# power.net
KiCad netlist of a schematic drawn in Altium Designer
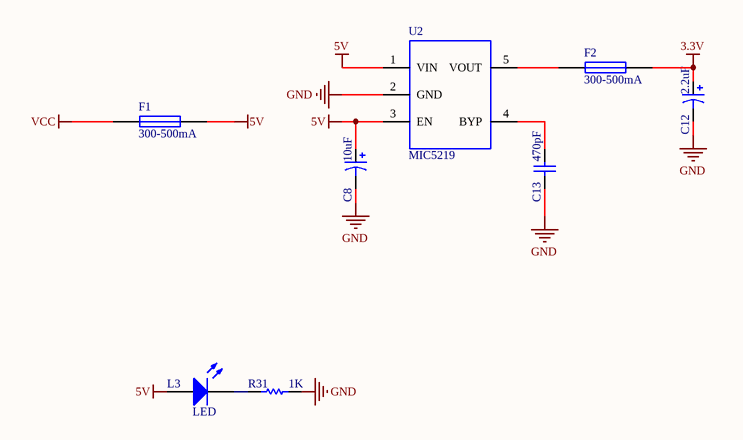
[diagram p0: power.SchDoc]

(export (version "E")
  (design (tool "Eeschema 10.0.6"))
  (components
    (comp (ref "C8")
      (value "10uF")
      (footprint "1206(2)")
      (description "Polarized Capacitor (Radial)")
      (fields (field (name "Comment") "Cap Pol1") (field (name "PUBLISHER") "Altium Limited"))
      (libsource (lib "Miscellaneous Devices") (part "Cap Pol1"))
    )
    (comp (ref "C12")
      (value "2.2uF")
      (footprint "1206(2)")
      (description "Polarized Capacitor (Radial)")
      (fields (field (name "Comment") "Cap Pol1") (field (name "PUBLISHER") "Altium Limited"))
      (libsource (lib "Miscellaneous Devices") (part "Cap Pol1"))
    )
    (comp (ref "C13")
      (value "470pF")
      (footprint "1608[0603]")
      (description "贴片电容")
      (fields (field (name "Comment") "Cap") (field (name "PUBLISHER") "Altium Limited"))
      (libsource (lib "Sparks") (part "Cap"))
    )
    (comp (ref "F1")
      (value "300-500mA")
      (footprint "1206(2)")
      (description "Fuse")
      (fields (field (name "PUBLISHER") "Altium Limited"))
      (libsource (lib "K60-V4.0") (part "Fuse 1"))
    )
    (comp (ref "F2")
      (value "300-500mA")
      (footprint "1206(2)")
      (description "Fuse")
      (fields (field (name "PUBLISHER") "Altium Limited"))
      (libsource (lib "K60-V4.0") (part "Fuse 1"))
    )
    (comp (ref "L3") (value "LED") (footprint "1608[0603]") (libsource (lib "Sparks") (part "LED")))
    (comp (ref "R31")
      (value "1K")
      (footprint "1608[0603]")
      (description "贴片电阻")
      (fields (field (name "Comment") "Res") (field (name "PUBLISHER") "Altium Limited"))
      (libsource (lib "Sparks") (part "Res"))
    )
    (comp (ref "U2")
      (value "MIC5219")
      (footprint "SOT-23-5")
      (description "LDO")
      (libsource (lib "K60-V4.0") (part "MIC5219"))
    )
  )
  (nets
    (net (code "1") (name "3.3V") (class "Default")
      (node (ref "C12") (pin "1") (pinfunction "1_1") (pintype "passive"))
      (node (ref "F2") (pin "2") (pinfunction "2_2") (pintype "passive"))
    )
    (net (code "2") (name "5V") (class "Default")
      (node (ref "C8") (pin "1") (pinfunction "1_1") (pintype "passive"))
      (node (ref "F1") (pin "2") (pinfunction "2_2") (pintype "passive"))
      (node (ref "L3") (pin "1") (pinfunction "A_1") (pintype "passive"))
      (node (ref "U2") (pin "1") (pinfunction "VIN_1") (pintype "passive"))
      (node (ref "U2") (pin "3") (pinfunction "EN_3") (pintype "passive"))
    )
    (net (code "3") (name "GND") (class "Default")
      (node (ref "C12") (pin "2") (pinfunction "2_2") (pintype "passive"))
      (node (ref "C13") (pin "1") (pinfunction "1_1") (pintype "passive"))
      (node (ref "C8") (pin "2") (pinfunction "2_2") (pintype "passive"))
      (node (ref "R31") (pin "1") (pinfunction "1_1") (pintype "passive"))
      (node (ref "U2") (pin "2") (pinfunction "GND_2") (pintype "passive"))
    )
    (net (code "4") (name "Net-(L3-K)") (class "Default")
      (node (ref "L3") (pin "2") (pinfunction "K_2") (pintype "passive"))
      (node (ref "R31") (pin "2") (pinfunction "2_2") (pintype "passive"))
    )
    (net (code "5") (name "Net-(U2-BYP)") (class "Default")
      (node (ref "C13") (pin "2") (pinfunction "2_2") (pintype "passive"))
      (node (ref "U2") (pin "4") (pinfunction "BYP_4") (pintype "passive"))
    )
    (net (code "6") (name "Net-(U2-VOUT)") (class "Default")
      (node (ref "F2") (pin "1") (pinfunction "1_1") (pintype "passive"))
      (node (ref "U2") (pin "5") (pinfunction "VOUT_5") (pintype "passive"))
    )
    (net (code "7") (name "VCC") (class "Default")
      (node (ref "F1") (pin "1") (pinfunction "1_1") (pintype "passive"))
    )
  )
)
